# ShardV3.net
KiCad netlist of a schematic drawn in EAGLE
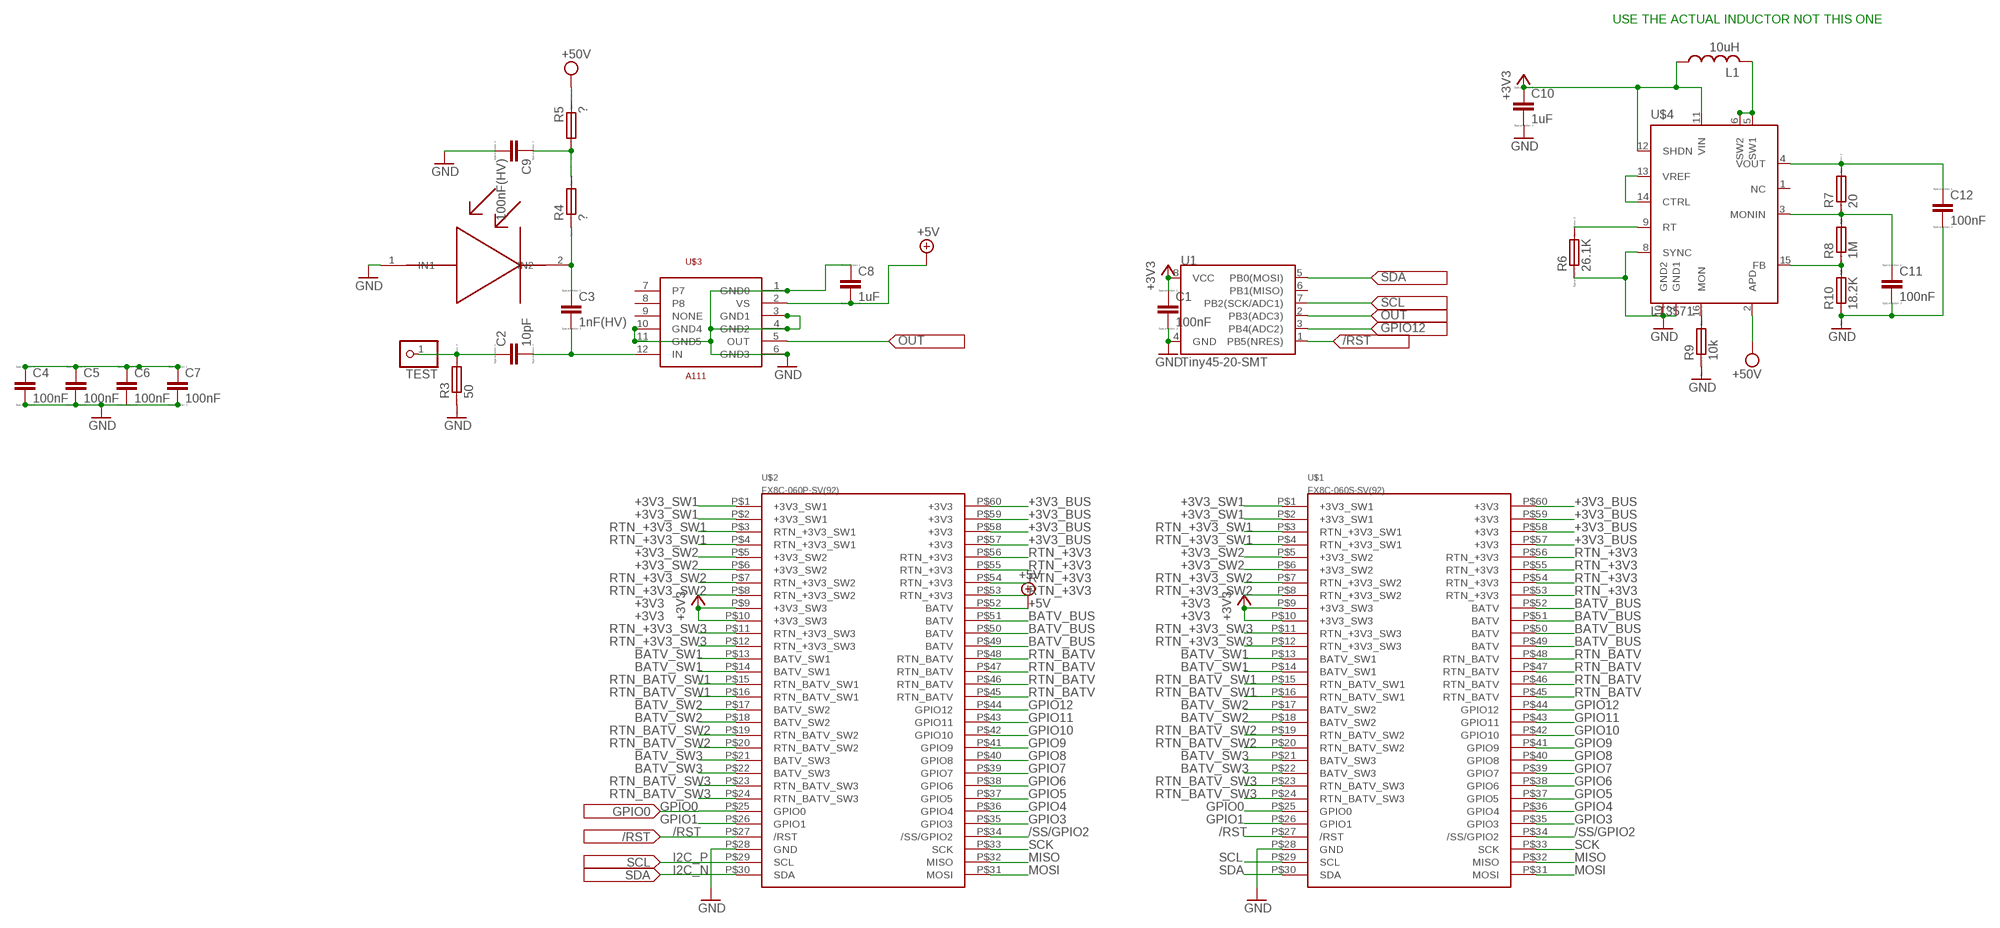
[diagram p0: schematic, sheet 1]

(export (version "E")
  (design (tool "Eeschema 10.0.6"))
  (components
    (comp (ref "C1")
      (value "100nF")
      (footprint "eagle-import:C0402")
      (libsource (lib "eagle-import") (part "CC0402"))
    )
    (comp (ref "C2")
      (value "10pF")
      (footprint "eagle-import:C0402")
      (libsource (lib "eagle-import") (part "CC0402"))
    )
    (comp (ref "C3")
      (value "1nF(HV)")
      (footprint "eagle-import:C0603")
      (libsource (lib "eagle-import") (part "CC0603"))
    )
    (comp (ref "C4")
      (value "100nF")
      (footprint "eagle-import:C0402")
      (libsource (lib "eagle-import") (part "CC0402"))
    )
    (comp (ref "C5")
      (value "100nF")
      (footprint "eagle-import:C0402")
      (libsource (lib "eagle-import") (part "CC0402"))
    )
    (comp (ref "C6")
      (value "100nF")
      (footprint "eagle-import:C0402")
      (libsource (lib "eagle-import") (part "CC0402"))
    )
    (comp (ref "C7")
      (value "100nF")
      (footprint "eagle-import:C0402")
      (libsource (lib "eagle-import") (part "CC0402"))
    )
    (comp (ref "C8")
      (value "1uF")
      (footprint "eagle-import:C0603")
      (libsource (lib "eagle-import") (part "CC0603"))
    )
    (comp (ref "C9")
      (value "100nF(HV)")
      (footprint "eagle-import:C0603")
      (libsource (lib "eagle-import") (part "CC0603"))
    )
    (comp (ref "C10")
      (value "1uF")
      (footprint "eagle-import:C0603")
      (libsource (lib "eagle-import") (part "CC0603"))
    )
    (comp (ref "C11")
      (value "100nF")
      (footprint "eagle-import:C0603")
      (libsource (lib "eagle-import") (part "CC0603"))
    )
    (comp (ref "C12")
      (value "100nF")
      (footprint "eagle-import:C0603")
      (libsource (lib "eagle-import") (part "CC0603"))
    )
    (comp (ref "L1")
      (value "10uH")
      (footprint "eagle-import:L1812")
      (libsource (lib "eagle-import") (part "L-USL1812"))
    )
    (comp (ref "NDD")
      (value "S3590-08")
      (footprint "eagle-import:S3590-08")
      (libsource (lib "eagle-import") (part "S3590-08"))
    )
    (comp (ref "R3")
      (value "50")
      (footprint "eagle-import:R0402")
      (libsource (lib "eagle-import") (part "RR0402"))
    )
    (comp (ref "R4")
      (value "?")
      (footprint "eagle-import:R0402")
      (libsource (lib "eagle-import") (part "RR0402"))
    )
    (comp (ref "R5")
      (value "?")
      (footprint "eagle-import:R0402")
      (libsource (lib "eagle-import") (part "RR0402"))
    )
    (comp (ref "R6")
      (value "26.1K")
      (footprint "eagle-import:R0402")
      (libsource (lib "eagle-import") (part "RR0402"))
    )
    (comp (ref "R7")
      (value "20")
      (footprint "eagle-import:R0402")
      (libsource (lib "eagle-import") (part "RR0402"))
    )
    (comp (ref "R8")
      (value "1M")
      (footprint "eagle-import:R0402")
      (libsource (lib "eagle-import") (part "RR0402"))
    )
    (comp (ref "R9")
      (value "10k")
      (footprint "eagle-import:R0402")
      (libsource (lib "eagle-import") (part "RR0402"))
    )
    (comp (ref "R10")
      (value "18.2K")
      (footprint "eagle-import:R0402")
      (libsource (lib "eagle-import") (part "RR0402"))
    )
    (comp (ref "TEST")
      (value "PINHD-1X1")
      (footprint "eagle-import:1X01")
      (libsource (lib "eagle-import") (part "PINHD-1X1"))
    )
    (comp (ref "U$1")
      (value "FX8C-060S-SV(92)")
      (footprint "eagle-import:FX8C-060S-SV(92)")
      (libsource (lib "eagle-import") (part "FX8C-060S-SV(92)"))
    )
    (comp (ref "U$2")
      (value "FX8C-060P-SV(92)")
      (footprint "eagle-import:FX8C-060P-SV(92)")
      (libsource (lib "eagle-import") (part "FX8C-060P-SV(92)"))
    )
    (comp (ref "U$3")
      (value "A111CHIP")
      (footprint "eagle-import:A111CHIP")
      (libsource (lib "eagle-import") (part "A111CHIP"))
    )
    (comp (ref "U$4")
      (value "LT3571")
      (footprint "eagle-import:QFN3X3-6")
      (libsource (lib "eagle-import") (part "LT3571"))
    )
    (comp (ref "U1")
      (value "Tiny45-20-SMT")
      (footprint "eagle-import:SO08-EIAJ")
      (libsource (lib "eagle-import") (part "ATTINY45TINY45-20-SMT"))
    )
  )
  (nets
    (net (code "1") (name "+3V3") (class "Default")
      (node (ref "C1") (pin "1") (pinfunction "1_1") (pintype "passive"))
      (node (ref "C10") (pin "1") (pinfunction "1_1") (pintype "passive"))
      (node (ref "L1") (pin "1") (pinfunction "1_1") (pintype "passive"))
      (node (ref "U$1") (pin "P$10") (pinfunction "+3V3_SW3_P$10") (pintype "power_in"))
      (node (ref "U$1") (pin "P$9") (pinfunction "+3V3_SW3_P$9") (pintype "power_in"))
      (node (ref "U$2") (pin "P$10") (pinfunction "+3V3_SW3_P$10") (pintype "power_in"))
      (node (ref "U$2") (pin "P$9") (pinfunction "+3V3_SW3_P$9") (pintype "power_in"))
      (node (ref "U$4") (pin "11") (pinfunction "VIN_11") (pintype "input"))
      (node (ref "U$4") (pin "12") (pinfunction "SHDN_12") (pintype "passive"))
      (node (ref "U1") (pin "8") (pinfunction "VCC_8") (pintype "bidirectional"))
    )
    (net (code "2") (name "+5V") (class "Default")
      (node (ref "C8") (pin "2") (pinfunction "2_2") (pintype "passive"))
      (node (ref "U$2") (pin "P$52") (pinfunction "BATV_P$52") (pintype "power_in"))
      (node (ref "U$3") (pin "2") (pinfunction "VS_2") (pintype "bidirectional"))
    )
    (net (code "3") (name "+50V") (class "Default")
      (node (ref "R5") (pin "1") (pinfunction "1_1") (pintype "passive"))
      (node (ref "U$4") (pin "2") (pinfunction "APD_2") (pintype "passive"))
    )
    (net (code "4") (name "/+3V3_BUS") (class "Default")
      (node (ref "U$1") (pin "P$57") (pinfunction "+3V3_P$57") (pintype "power_in"))
      (node (ref "U$1") (pin "P$58") (pinfunction "+3V3_P$58") (pintype "power_in"))
      (node (ref "U$1") (pin "P$59") (pinfunction "+3V3_P$59") (pintype "power_in"))
      (node (ref "U$1") (pin "P$60") (pinfunction "+3V3_P$60") (pintype "power_in"))
      (node (ref "U$2") (pin "P$57") (pinfunction "+3V3_P$57") (pintype "power_in"))
      (node (ref "U$2") (pin "P$58") (pinfunction "+3V3_P$58") (pintype "power_in"))
      (node (ref "U$2") (pin "P$59") (pinfunction "+3V3_P$59") (pintype "power_in"))
      (node (ref "U$2") (pin "P$60") (pinfunction "+3V3_P$60") (pintype "power_in"))
    )
    (net (code "5") (name "/+3V3_SW1") (class "Default")
      (node (ref "U$1") (pin "P$1") (pinfunction "+3V3_SW1_P$1") (pintype "power_in"))
      (node (ref "U$1") (pin "P$2") (pinfunction "+3V3_SW1_P$2") (pintype "power_in"))
      (node (ref "U$2") (pin "P$1") (pinfunction "+3V3_SW1_P$1") (pintype "power_in"))
      (node (ref "U$2") (pin "P$2") (pinfunction "+3V3_SW1_P$2") (pintype "power_in"))
    )
    (net (code "6") (name "/+3V3_SW2") (class "Default")
      (node (ref "U$1") (pin "P$5") (pinfunction "+3V3_SW2_P$5") (pintype "power_in"))
      (node (ref "U$1") (pin "P$6") (pinfunction "+3V3_SW2_P$6") (pintype "power_in"))
      (node (ref "U$2") (pin "P$5") (pinfunction "+3V3_SW2_P$5") (pintype "power_in"))
      (node (ref "U$2") (pin "P$6") (pinfunction "+3V3_SW2_P$6") (pintype "power_in"))
    )
    (net (code "7") (name "/BATV_BUS") (class "Default")
      (node (ref "U$1") (pin "P$49") (pinfunction "BATV_P$49") (pintype "power_in"))
      (node (ref "U$1") (pin "P$50") (pinfunction "BATV_P$50") (pintype "power_in"))
      (node (ref "U$1") (pin "P$51") (pinfunction "BATV_P$51") (pintype "power_in"))
      (node (ref "U$1") (pin "P$52") (pinfunction "BATV_P$52") (pintype "power_in"))
      (node (ref "U$2") (pin "P$49") (pinfunction "BATV_P$49") (pintype "power_in"))
      (node (ref "U$2") (pin "P$50") (pinfunction "BATV_P$50") (pintype "power_in"))
      (node (ref "U$2") (pin "P$51") (pinfunction "BATV_P$51") (pintype "power_in"))
    )
    (net (code "8") (name "/BATV_SW1") (class "Default")
      (node (ref "U$1") (pin "P$13") (pinfunction "BATV_SW1_P$13") (pintype "power_in"))
      (node (ref "U$1") (pin "P$14") (pinfunction "BATV_SW1_P$14") (pintype "power_in"))
      (node (ref "U$2") (pin "P$13") (pinfunction "BATV_SW1_P$13") (pintype "power_in"))
      (node (ref "U$2") (pin "P$14") (pinfunction "BATV_SW1_P$14") (pintype "power_in"))
    )
    (net (code "9") (name "/BATV_SW2") (class "Default")
      (node (ref "U$1") (pin "P$17") (pinfunction "BATV_SW2_P$17") (pintype "power_in"))
      (node (ref "U$1") (pin "P$18") (pinfunction "BATV_SW2_P$18") (pintype "power_in"))
      (node (ref "U$2") (pin "P$17") (pinfunction "BATV_SW2_P$17") (pintype "power_in"))
      (node (ref "U$2") (pin "P$18") (pinfunction "BATV_SW2_P$18") (pintype "power_in"))
    )
    (net (code "10") (name "/BATV_SW3") (class "Default")
      (node (ref "U$1") (pin "P$21") (pinfunction "BATV_SW3_P$21") (pintype "power_in"))
      (node (ref "U$1") (pin "P$22") (pinfunction "BATV_SW3_P$22") (pintype "power_in"))
      (node (ref "U$2") (pin "P$21") (pinfunction "BATV_SW3_P$21") (pintype "power_in"))
      (node (ref "U$2") (pin "P$22") (pinfunction "BATV_SW3_P$22") (pintype "power_in"))
    )
    (net (code "11") (name "/GPIO0") (class "Default")
      (node (ref "U$1") (pin "P$25") (pinfunction "GPIO0_P$25") (pintype "bidirectional"))
      (node (ref "U$2") (pin "P$25") (pinfunction "GPIO0_P$25") (pintype "bidirectional"))
    )
    (net (code "12") (name "/GPIO1") (class "Default")
      (node (ref "U$1") (pin "P$26") (pinfunction "GPIO1_P$26") (pintype "bidirectional"))
      (node (ref "U$2") (pin "P$26") (pinfunction "GPIO1_P$26") (pintype "bidirectional"))
    )
    (net (code "13") (name "/GPIO3") (class "Default")
      (node (ref "U$1") (pin "P$35") (pinfunction "GPIO3_P$35") (pintype "bidirectional"))
      (node (ref "U$2") (pin "P$35") (pinfunction "GPIO3_P$35") (pintype "bidirectional"))
    )
    (net (code "14") (name "/GPIO4") (class "Default")
      (node (ref "U$1") (pin "P$36") (pinfunction "GPIO4_P$36") (pintype "bidirectional"))
      (node (ref "U$2") (pin "P$36") (pinfunction "GPIO4_P$36") (pintype "bidirectional"))
    )
    (net (code "15") (name "/GPIO5") (class "Default")
      (node (ref "U$1") (pin "P$37") (pinfunction "GPIO5_P$37") (pintype "bidirectional"))
      (node (ref "U$2") (pin "P$37") (pinfunction "GPIO5_P$37") (pintype "bidirectional"))
    )
    (net (code "16") (name "/GPIO6") (class "Default")
      (node (ref "U$1") (pin "P$38") (pinfunction "GPIO6_P$38") (pintype "bidirectional"))
      (node (ref "U$2") (pin "P$38") (pinfunction "GPIO6_P$38") (pintype "bidirectional"))
    )
    (net (code "17") (name "/GPIO7") (class "Default")
      (node (ref "U$1") (pin "P$39") (pinfunction "GPIO7_P$39") (pintype "bidirectional"))
      (node (ref "U$2") (pin "P$39") (pinfunction "GPIO7_P$39") (pintype "bidirectional"))
    )
    (net (code "18") (name "/GPIO8") (class "Default")
      (node (ref "U$1") (pin "P$40") (pinfunction "GPIO8_P$40") (pintype "bidirectional"))
      (node (ref "U$2") (pin "P$40") (pinfunction "GPIO8_P$40") (pintype "bidirectional"))
    )
    (net (code "19") (name "/GPIO9") (class "Default")
      (node (ref "U$1") (pin "P$41") (pinfunction "GPIO9_P$41") (pintype "bidirectional"))
      (node (ref "U$2") (pin "P$41") (pinfunction "GPIO9_P$41") (pintype "bidirectional"))
    )
    (net (code "20") (name "/GPIO10") (class "Default")
      (node (ref "U$1") (pin "P$42") (pinfunction "GPIO10_P$42") (pintype "bidirectional"))
      (node (ref "U$2") (pin "P$42") (pinfunction "GPIO10_P$42") (pintype "bidirectional"))
    )
    (net (code "21") (name "/GPIO11") (class "Default")
      (node (ref "U$1") (pin "P$43") (pinfunction "GPIO11_P$43") (pintype "bidirectional"))
      (node (ref "U$2") (pin "P$43") (pinfunction "GPIO11_P$43") (pintype "bidirectional"))
    )
    (net (code "22") (name "/GPIO12") (class "Default")
      (node (ref "U$1") (pin "P$44") (pinfunction "GPIO12_P$44") (pintype "bidirectional"))
      (node (ref "U$2") (pin "P$44") (pinfunction "GPIO12_P$44") (pintype "bidirectional"))
      (node (ref "U1") (pin "3") (pinfunction "PB4(ADC2)_3") (pintype "bidirectional"))
    )
    (net (code "23") (name "/I2C_N") (class "Default")
      (node (ref "U$2") (pin "P$30") (pinfunction "SDA_P$30") (pintype "bidirectional"))
      (node (ref "U1") (pin "5") (pinfunction "PB0(MOSI)_5") (pintype "bidirectional"))
    )
    (net (code "24") (name "/I2C_P") (class "Default")
      (node (ref "U$2") (pin "P$29") (pinfunction "SCL_P$29") (pintype "bidirectional"))
      (node (ref "U1") (pin "7") (pinfunction "PB2(SCK/ADC1)_7") (pintype "bidirectional"))
    )
    (net (code "25") (name "/MISO") (class "Default")
      (node (ref "U$1") (pin "P$32") (pinfunction "MISO_P$32") (pintype "bidirectional"))
      (node (ref "U$2") (pin "P$32") (pinfunction "MISO_P$32") (pintype "bidirectional"))
    )
    (net (code "26") (name "/MOSI") (class "Default")
      (node (ref "U$1") (pin "P$31") (pinfunction "MOSI_P$31") (pintype "bidirectional"))
      (node (ref "U$2") (pin "P$31") (pinfunction "MOSI_P$31") (pintype "bidirectional"))
    )
    (net (code "27") (name "/OUT") (class "Default")
      (node (ref "U$3") (pin "5") (pinfunction "OUT_5") (pintype "bidirectional"))
      (node (ref "U1") (pin "2") (pinfunction "PB3(ADC3)_2") (pintype "bidirectional"))
    )
    (net (code "28") (name "/RTN_+3V3") (class "Default")
      (node (ref "U$1") (pin "P$53") (pinfunction "RTN_+3V3_P$53") (pintype "power_in"))
      (node (ref "U$1") (pin "P$54") (pinfunction "RTN_+3V3_P$54") (pintype "power_in"))
      (node (ref "U$1") (pin "P$55") (pinfunction "RTN_+3V3_P$55") (pintype "power_in"))
      (node (ref "U$1") (pin "P$56") (pinfunction "RTN_+3V3_P$56") (pintype "power_in"))
      (node (ref "U$2") (pin "P$53") (pinfunction "RTN_+3V3_P$53") (pintype "power_in"))
      (node (ref "U$2") (pin "P$54") (pinfunction "RTN_+3V3_P$54") (pintype "power_in"))
      (node (ref "U$2") (pin "P$55") (pinfunction "RTN_+3V3_P$55") (pintype "power_in"))
      (node (ref "U$2") (pin "P$56") (pinfunction "RTN_+3V3_P$56") (pintype "power_in"))
    )
    (net (code "29") (name "/RTN_+3V3_SW1") (class "Default")
      (node (ref "U$1") (pin "P$3") (pinfunction "RTN_+3V3_SW1_P$3") (pintype "power_in"))
      (node (ref "U$1") (pin "P$4") (pinfunction "RTN_+3V3_SW1_P$4") (pintype "power_in"))
      (node (ref "U$2") (pin "P$3") (pinfunction "RTN_+3V3_SW1_P$3") (pintype "power_in"))
      (node (ref "U$2") (pin "P$4") (pinfunction "RTN_+3V3_SW1_P$4") (pintype "power_in"))
    )
    (net (code "30") (name "/RTN_+3V3_SW2") (class "Default")
      (node (ref "U$1") (pin "P$7") (pinfunction "RTN_+3V3_SW2_P$7") (pintype "power_in"))
      (node (ref "U$1") (pin "P$8") (pinfunction "RTN_+3V3_SW2_P$8") (pintype "power_in"))
      (node (ref "U$2") (pin "P$7") (pinfunction "RTN_+3V3_SW2_P$7") (pintype "power_in"))
      (node (ref "U$2") (pin "P$8") (pinfunction "RTN_+3V3_SW2_P$8") (pintype "power_in"))
    )
    (net (code "31") (name "/RTN_+3V3_SW3") (class "Default")
      (node (ref "U$1") (pin "P$11") (pinfunction "RTN_+3V3_SW3_P$11") (pintype "power_in"))
      (node (ref "U$1") (pin "P$12") (pinfunction "RTN_+3V3_SW3_P$12") (pintype "power_in"))
      (node (ref "U$2") (pin "P$11") (pinfunction "RTN_+3V3_SW3_P$11") (pintype "power_in"))
      (node (ref "U$2") (pin "P$12") (pinfunction "RTN_+3V3_SW3_P$12") (pintype "power_in"))
    )
    (net (code "32") (name "/RTN_BATV") (class "Default")
      (node (ref "U$1") (pin "P$45") (pinfunction "RTN_BATV_P$45") (pintype "power_in"))
      (node (ref "U$1") (pin "P$46") (pinfunction "RTN_BATV_P$46") (pintype "power_in"))
      (node (ref "U$1") (pin "P$47") (pinfunction "RTN_BATV_P$47") (pintype "power_in"))
      (node (ref "U$1") (pin "P$48") (pinfunction "RTN_BATV_P$48") (pintype "power_in"))
      (node (ref "U$2") (pin "P$45") (pinfunction "RTN_BATV_P$45") (pintype "power_in"))
      (node (ref "U$2") (pin "P$46") (pinfunction "RTN_BATV_P$46") (pintype "power_in"))
      (node (ref "U$2") (pin "P$47") (pinfunction "RTN_BATV_P$47") (pintype "power_in"))
      (node (ref "U$2") (pin "P$48") (pinfunction "RTN_BATV_P$48") (pintype "power_in"))
    )
    (net (code "33") (name "/RTN_BATV_SW1") (class "Default")
      (node (ref "U$1") (pin "P$15") (pinfunction "RTN_BATV_SW1_P$15") (pintype "power_in"))
      (node (ref "U$1") (pin "P$16") (pinfunction "RTN_BATV_SW1_P$16") (pintype "power_in"))
      (node (ref "U$2") (pin "P$15") (pinfunction "RTN_BATV_SW1_P$15") (pintype "power_in"))
      (node (ref "U$2") (pin "P$16") (pinfunction "RTN_BATV_SW1_P$16") (pintype "power_in"))
    )
    (net (code "34") (name "/RTN_BATV_SW2") (class "Default")
      (node (ref "U$1") (pin "P$19") (pinfunction "RTN_BATV_SW2_P$19") (pintype "power_in"))
      (node (ref "U$1") (pin "P$20") (pinfunction "RTN_BATV_SW2_P$20") (pintype "power_in"))
      (node (ref "U$2") (pin "P$19") (pinfunction "RTN_BATV_SW2_P$19") (pintype "power_in"))
      (node (ref "U$2") (pin "P$20") (pinfunction "RTN_BATV_SW2_P$20") (pintype "power_in"))
    )
    (net (code "35") (name "/RTN_BATV_SW3") (class "Default")
      (node (ref "U$1") (pin "P$23") (pinfunction "RTN_BATV_SW3_P$23") (pintype "power_in"))
      (node (ref "U$1") (pin "P$24") (pinfunction "RTN_BATV_SW3_P$24") (pintype "power_in"))
      (node (ref "U$2") (pin "P$23") (pinfunction "RTN_BATV_SW3_P$23") (pintype "power_in"))
      (node (ref "U$2") (pin "P$24") (pinfunction "RTN_BATV_SW3_P$24") (pintype "power_in"))
    )
    (net (code "36") (name "/SCK") (class "Default")
      (node (ref "U$1") (pin "P$33") (pinfunction "SCK_P$33") (pintype "bidirectional"))
      (node (ref "U$2") (pin "P$33") (pinfunction "SCK_P$33") (pintype "bidirectional"))
    )
    (net (code "37") (name "/SCL") (class "Default")
      (node (ref "U$1") (pin "P$29") (pinfunction "SCL_P$29") (pintype "bidirectional"))
    )
    (net (code "38") (name "/SDA") (class "Default")
      (node (ref "U$1") (pin "P$30") (pinfunction "SDA_P$30") (pintype "bidirectional"))
    )
    (net (code "39") (name "/{slash}RST") (class "Default")
      (node (ref "U$1") (pin "P$27") (pinfunction "/RST_P$27") (pintype "bidirectional"))
      (node (ref "U$2") (pin "P$27") (pinfunction "/RST_P$27") (pintype "bidirectional"))
      (node (ref "U1") (pin "1") (pinfunction "PB5(NRES)_1") (pintype "bidirectional"))
    )
    (net (code "40") (name "/{slash}SS{slash}GPIO2") (class "Default")
      (node (ref "U$1") (pin "P$34") (pinfunction "/SS/GPIO2_P$34") (pintype "bidirectional"))
      (node (ref "U$2") (pin "P$34") (pinfunction "/SS/GPIO2_P$34") (pintype "bidirectional"))
    )
    (net (code "41") (name "GND") (class "Default")
      (node (ref "C1") (pin "2") (pinfunction "2_2") (pintype "passive"))
      (node (ref "C10") (pin "2") (pinfunction "2_2") (pintype "passive"))
      (node (ref "C11") (pin "2") (pinfunction "2_2") (pintype "passive"))
      (node (ref "C12") (pin "2") (pinfunction "2_2") (pintype "passive"))
      (node (ref "C4") (pin "2") (pinfunction "2_2") (pintype "passive"))
      (node (ref "C5") (pin "2") (pinfunction "2_2") (pintype "passive"))
      (node (ref "C7") (pin "2") (pinfunction "2_2") (pintype "passive"))
      (node (ref "C8") (pin "1") (pinfunction "1_1") (pintype "passive"))
      (node (ref "C9") (pin "2") (pinfunction "2_2") (pintype "passive"))
      (node (ref "NDD") (pin "1") (pinfunction "IN1_1") (pintype "bidirectional"))
      (node (ref "R10") (pin "1") (pinfunction "1_1") (pintype "passive"))
      (node (ref "R3") (pin "1") (pinfunction "1_1") (pintype "passive"))
      (node (ref "R6") (pin "1") (pinfunction "1_1") (pintype "passive"))
      (node (ref "R9") (pin "1") (pinfunction "1_1") (pintype "passive"))
      (node (ref "U$1") (pin "P$28") (pinfunction "GND_P$28") (pintype "bidirectional"))
      (node (ref "U$2") (pin "P$28") (pinfunction "GND_P$28") (pintype "bidirectional"))
      (node (ref "U$3") (pin "1") (pinfunction "GND0_1") (pintype "bidirectional"))
      (node (ref "U$3") (pin "10") (pinfunction "GND4_10") (pintype "bidirectional"))
      (node (ref "U$3") (pin "11") (pinfunction "GND5_11") (pintype "bidirectional"))
      (node (ref "U$3") (pin "3") (pinfunction "GND1_3") (pintype "bidirectional"))
      (node (ref "U$3") (pin "4") (pinfunction "GND2_4") (pintype "bidirectional"))
      (node (ref "U$3") (pin "6") (pinfunction "GND3_6") (pintype "bidirectional"))
      (node (ref "U$4") (pin "10") (pinfunction "GND2_10") (pintype "input"))
      (node (ref "U$4") (pin "7") (pinfunction "GND1_7") (pintype "open_collector"))
      (node (ref "U$4") (pin "8") (pinfunction "SYNC_8") (pintype "input"))
      (node (ref "U1") (pin "4") (pinfunction "GND_4") (pintype "bidirectional"))
    )
    (net (code "42") (name "Net-(C2-Pad1)") (class "Default")
      (node (ref "C2") (pin "1") (pinfunction "1_1") (pintype "passive"))
      (node (ref "R3") (pin "2") (pinfunction "2_2") (pintype "passive"))
      (node (ref "TEST") (pin "1") (pinfunction "1_1") (pintype "passive"))
    )
    (net (code "43") (name "Net-(C4-Pad1)") (class "Default")
      (node (ref "C4") (pin "1") (pinfunction "1_1") (pintype "passive"))
      (node (ref "C5") (pin "1") (pinfunction "1_1") (pintype "passive"))
      (node (ref "C6") (pin "1") (pinfunction "1_1") (pintype "passive"))
      (node (ref "C7") (pin "1") (pinfunction "1_1") (pintype "passive"))
    )
    (net (code "44") (name "Net-(C9-Pad1)") (class "Default")
      (node (ref "C9") (pin "1") (pinfunction "1_1") (pintype "passive"))
      (node (ref "R4") (pin "2") (pinfunction "2_2") (pintype "passive"))
      (node (ref "R5") (pin "2") (pinfunction "2_2") (pintype "passive"))
    )
    (net (code "45") (name "Net-(NDD-IN2)") (class "Default")
      (node (ref "C3") (pin "1") (pinfunction "1_1") (pintype "passive"))
      (node (ref "NDD") (pin "2") (pinfunction "IN2_2") (pintype "bidirectional"))
      (node (ref "R4") (pin "1") (pinfunction "1_1") (pintype "passive"))
    )
    (net (code "46") (name "Net-(U$3-IN)") (class "Default")
      (node (ref "C2") (pin "2") (pinfunction "2_2") (pintype "passive"))
      (node (ref "C3") (pin "2") (pinfunction "2_2") (pintype "passive"))
      (node (ref "U$3") (pin "12") (pinfunction "IN_12") (pintype "bidirectional"))
    )
    (net (code "47") (name "Net-(U$4-CTRL)") (class "Default")
      (node (ref "U$4") (pin "13") (pinfunction "VREF_13") (pintype "output"))
      (node (ref "U$4") (pin "14") (pinfunction "CTRL_14") (pintype "input"))
    )
    (net (code "48") (name "Net-(U$4-FB)") (class "Default")
      (node (ref "R10") (pin "2") (pinfunction "2_2") (pintype "passive"))
      (node (ref "R8") (pin "1") (pinfunction "1_1") (pintype "passive"))
      (node (ref "U$4") (pin "15") (pinfunction "FB_15") (pintype "input"))
    )
    (net (code "49") (name "Net-(U$4-MON)") (class "Default")
      (node (ref "R9") (pin "2") (pinfunction "2_2") (pintype "passive"))
      (node (ref "U$4") (pin "16") (pinfunction "MON_16") (pintype "input"))
    )
    (net (code "50") (name "Net-(U$4-MONIN)") (class "Default")
      (node (ref "C11") (pin "1") (pinfunction "1_1") (pintype "passive"))
      (node (ref "R7") (pin "1") (pinfunction "1_1") (pintype "passive"))
      (node (ref "R8") (pin "2") (pinfunction "2_2") (pintype "passive"))
      (node (ref "U$4") (pin "3") (pinfunction "MONIN_3") (pintype "passive"))
    )
    (net (code "51") (name "Net-(U$4-RT)") (class "Default")
      (node (ref "R6") (pin "2") (pinfunction "2_2") (pintype "passive"))
      (node (ref "U$4") (pin "9") (pinfunction "RT_9") (pintype "input"))
    )
    (net (code "52") (name "Net-(U$4-SW1)") (class "Default")
      (node (ref "L1") (pin "2") (pinfunction "2_2") (pintype "passive"))
      (node (ref "U$4") (pin "5") (pinfunction "SW1_5") (pintype "power_in"))
      (node (ref "U$4") (pin "6") (pinfunction "SW2_6") (pintype "power_in"))
    )
    (net (code "53") (name "Net-(U$4-VOUT)") (class "Default")
      (node (ref "C12") (pin "1") (pinfunction "1_1") (pintype "passive"))
      (node (ref "R7") (pin "2") (pinfunction "2_2") (pintype "passive"))
      (node (ref "U$4") (pin "4") (pinfunction "VOUT_4") (pintype "input"))
    )
    (net (code "54") (name "unconnected-(C6-Pad2)") (class "Default")
      (node (ref "C6") (pin "2") (pinfunction "2_2") (pintype "passive"))
    )
    (net (code "55") (name "unconnected-(U$3-NONE-Pad9)") (class "Default")
      (node (ref "U$3") (pin "9") (pinfunction "NONE_9") (pintype "bidirectional"))
    )
    (net (code "56") (name "unconnected-(U$3-P7-Pad7)") (class "Default")
      (node (ref "U$3") (pin "7") (pinfunction "P7_7") (pintype "bidirectional"))
    )
    (net (code "57") (name "unconnected-(U$3-P8-Pad8)") (class "Default")
      (node (ref "U$3") (pin "8") (pinfunction "P8_8") (pintype "bidirectional"))
    )
    (net (code "58") (name "unconnected-(U$4-NC-Pad1)") (class "Default")
      (node (ref "U$4") (pin "1") (pinfunction "NC_1") (pintype "input"))
    )
    (net (code "59") (name "unconnected-(U1-PB1(MISO)-Pad6)") (class "Default")
      (node (ref "U1") (pin "6") (pinfunction "PB1(MISO)_6") (pintype "bidirectional"))
    )
  )
)
